# stm32f103.net
KiCad netlist of a schematic drawn in Altium Designer
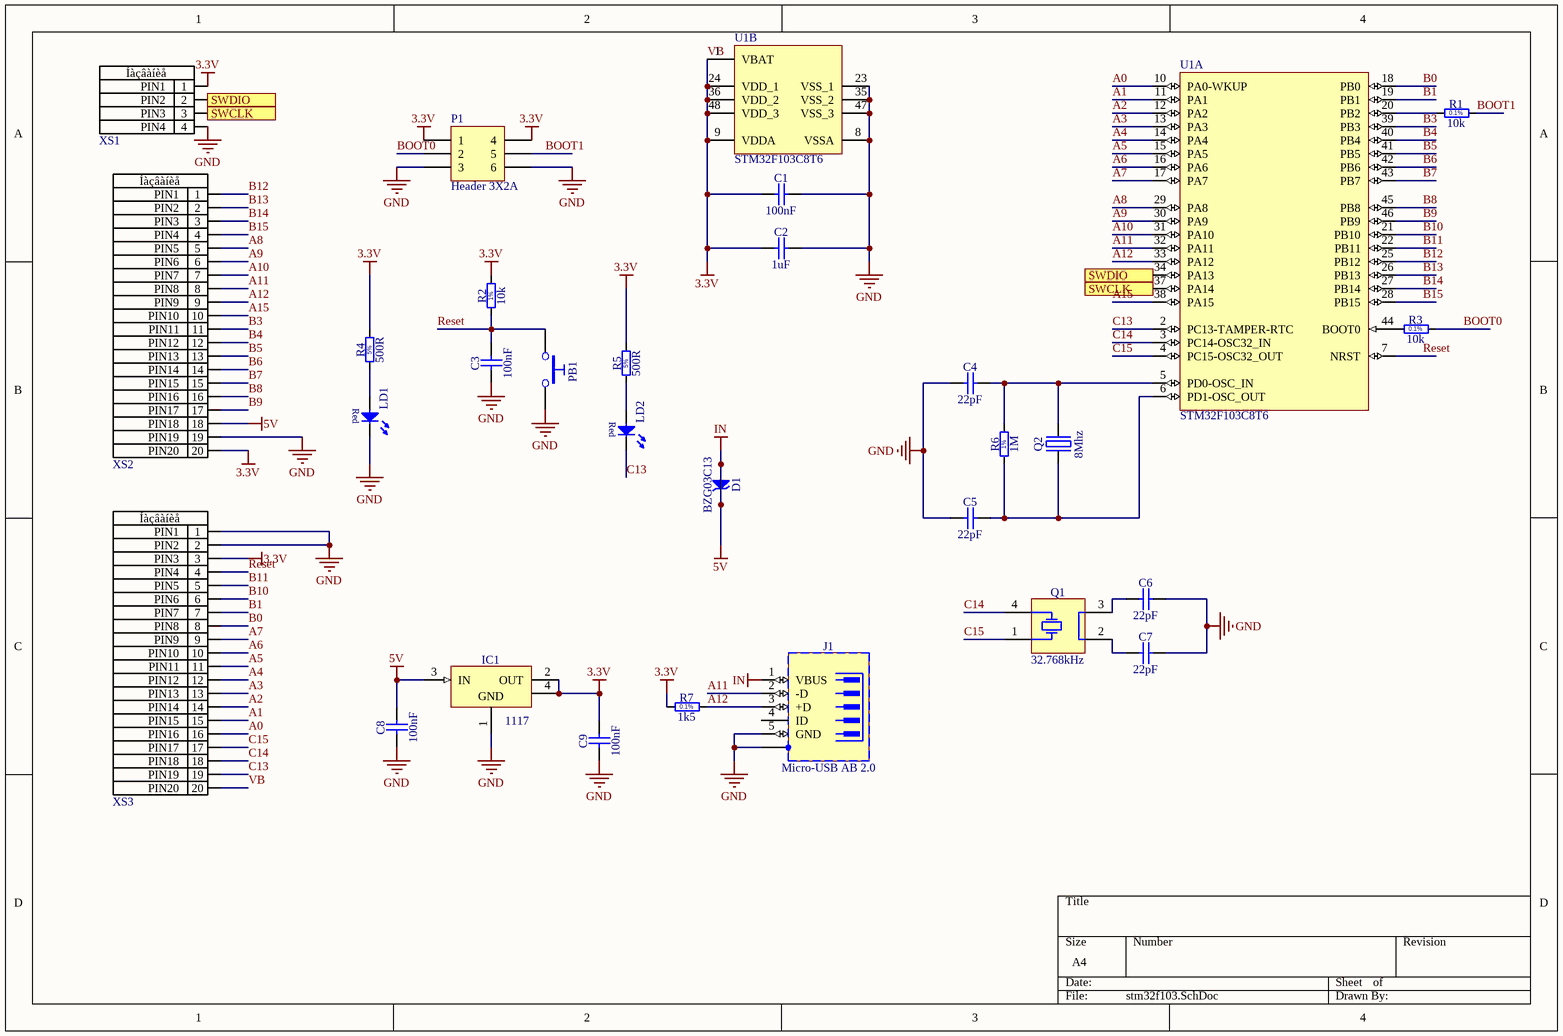
[diagram p0: stm32f103.SchDoc]

(export (version "E")
  (design (tool "Eeschema 10.0.6"))
  (components
    (comp (ref "C1")
      (value "100nF")
      (footprint "CAPC3216X140N")
      (description "Non-polarised capacitor")
      (fields
        (field (name "PART NUMBER") "CC1206_100NF_50V_10%_X7R")
        (field (name "VOLTAGE") "50V")
        (field (name "AUTHOR") "CERN DEM JLC")
      )
      (libsource (lib "Capacitors") (part "Capacitor - non polarized"))
    )
    (comp (ref "C2")
      (value "1uF")
      (footprint "CAPC3216X140N")
      (description "Non-polarised capacitor")
      (fields
        (field (name "PART NUMBER") "CC1206_1UF_50V_10%_X7R")
        (field (name "VOLTAGE") "50V")
        (field (name "AUTHOR") "CERN DEM JLC")
      )
      (libsource (lib "Capacitors") (part "Capacitor - non polarized"))
    )
    (comp (ref "C3")
      (value "100nF")
      (footprint "CAPC3216X140N")
      (description "Non-polarised capacitor")
      (fields
        (field (name "PART NUMBER") "CC1206_100NF_50V_10%_X7R")
        (field (name "VOLTAGE") "50V")
        (field (name "AUTHOR") "CERN DEM JLC")
      )
      (libsource (lib "Capacitors") (part "Capacitor - non polarized"))
    )
    (comp (ref "C4")
      (value "22pF")
      (footprint "CAPC3216X140N")
      (description "Non-polarised capacitor")
      (fields
        (field (name "PART NUMBER") "CC1206_12PF_50V_5%_NP0")
        (field (name "VOLTAGE") "50V")
        (field (name "AUTHOR") "CERN DEM JLC")
      )
      (libsource (lib "Capacitors") (part "Capacitor - non polarized"))
    )
    (comp (ref "C5")
      (value "22pF")
      (footprint "CAPC3216X140N")
      (description "Non-polarised capacitor")
      (fields
        (field (name "PART NUMBER") "CC1206_12PF_50V_5%_NP0")
        (field (name "VOLTAGE") "50V")
        (field (name "AUTHOR") "CERN DEM JLC")
      )
      (libsource (lib "Capacitors") (part "Capacitor - non polarized"))
    )
    (comp (ref "C6")
      (value "22pF")
      (footprint "CAPC3216X140N")
      (description "Non-polarised capacitor")
      (fields
        (field (name "PART NUMBER") "CC1206_100PF_50V_5%_NP0")
        (field (name "VOLTAGE") "50V")
        (field (name "AUTHOR") "CERN DEM JLC")
      )
      (libsource (lib "Capacitors") (part "Capacitor - non polarized"))
    )
    (comp (ref "C7")
      (value "22pF")
      (footprint "CAPC3216X140N")
      (description "Non-polarised capacitor")
      (fields
        (field (name "PART NUMBER") "CC1206_100PF_50V_5%_NP0")
        (field (name "VOLTAGE") "50V")
        (field (name "AUTHOR") "CERN DEM JLC")
      )
      (libsource (lib "Capacitors") (part "Capacitor - non polarized"))
    )
    (comp (ref "C8")
      (value "100nF")
      (footprint "CAPC3216X140N")
      (description "Non-polarised capacitor")
      (fields
        (field (name "PART NUMBER") "CC1206_100NF_50V_10%_X7R")
        (field (name "VOLTAGE") "50V")
        (field (name "AUTHOR") "CERN DEM JLC")
      )
      (libsource (lib "Capacitors") (part "Capacitor - non polarized"))
    )
    (comp (ref "C9")
      (value "100nF")
      (footprint "CAPC3216X140N")
      (description "Non-polarised capacitor")
      (fields
        (field (name "PART NUMBER") "CC1206_100NF_50V_10%_X7R")
        (field (name "VOLTAGE") "50V")
        (field (name "AUTHOR") "CERN DEM JLC")
      )
      (libsource (lib "Capacitors") (part "Capacitor - non polarized"))
    )
    (comp (ref "D1")
      (value "BZG03C13")
      (footprint "DIOM5326X230N")
      (description "Zener Diode")
      (fields
        (field (name "VOLTAGE") "13V")
        (field (name "POWER") "1.25W")
        (field (name "AUTHOR") "CERN DEM JLC")
      )
      (libsource (lib "ICs And Semiconductors") (part "Diode Zener"))
    )
    (comp (ref "IC1")
      (value "1117")
      (footprint "SOT230P700X180-4N")
      (description "3-Terminal Regulator 1=GND 2=OUT 3=IN 4=OUT")
      (fields
        (field (name "PART NUMBER") "ADP3339AKCZ-1.8")
        (field (name "MANUFACTURER") "ANALOG DEVICES")
        (field (name "AUTHOR") "CERN DEM BC")
      )
      (libsource (lib "ICs And Semiconductors") (part "REG3+1 1GND-2OUT-3IN+4OUT"))
    )
    (comp (ref "J1")
      (value "Micro-USB AB 2.0")
      (footprint "HIROSE_ZX62RD-AB-5P8(30)")
      (description "5 Pin + 1 Shield USB Receptacle")
      (fields
        (field (name "PART NUMBER") "HIROSE_ZX62RD-AB-5P8(30)")
        (field (name "MANUFACTURER") "HIROSE (HRS)")
        (field (name "AUTHOR") "CERN DEM JMW")
      )
      (libsource (lib "Connectors") (part "Connector USB 5 Pin + 1Shield"))
    )
    (comp (ref "LD1")
      (value "Red")
      (footprint "LED_DIALIGHT_597-3111-507F")
      (description "LED Red 1C 2A")
      (fields
        (field (name "PART NUMBER") "LED_DIALIGHT_597-3111-507F")
        (field (name "MANUFACTURER") "DIALIGHT")
        (field (name "AUTHOR") "CERN DEM JLC")
      )
      (libsource (lib "ICs And Semiconductors") (part "LED Red 1C 2A"))
    )
    (comp (ref "LD2")
      (value "Red")
      (footprint "LED_DIALIGHT_597-3111-507F")
      (description "LED Red 1C 2A")
      (fields
        (field (name "PART NUMBER") "LED_DIALIGHT_597-3111-507F")
        (field (name "MANUFACTURER") "DIALIGHT")
        (field (name "AUTHOR") "CERN DEM JLC")
      )
      (libsource (lib "ICs And Semiconductors") (part "LED Red 1C 2A"))
    )
    (comp (ref "P1")
      (value "Header 3X2A")
      (footprint "HDR2X3_CEN")
      (description "Header, 3-Pin, Dual row")
      (fields (field (name "PUBLISHER") "Altium Limited"))
      (libsource (lib "Miscellaneous Connectors") (part "Header 3X2A"))
    )
    (comp (ref "PB1")
      (value "Push Button")
      (footprint "PB_TYCO_FSMSM")
      (description "Push-Button Switch SPDT")
      (fields
        (field (name "PART NUMBER") "PB_TYCO_FSMSM")
        (field (name "MANUFACTURER") "TYCO ELECTRONICS")
        (field (name "AUTHOR") "CERN DEM JLC")
      )
      (libsource (lib "Eletro-mechanical") (part "PB SPST 1NO-2NO"))
    )
    (comp (ref "Q1")
      (value "32.768kHz")
      (footprint "XTAL_ABRACON_ABS25")
      (description "Crystal 4 pins 1=XTAL Control 2 And 3=NC 4=XTAL")
      (fields
        (field (name "PART NUMBER") "XTAL_32.768KHZ_ABRACON_ABS25-32.768KHZ-T")
        (field (name "MANUFACTURER") "ABRACON")
        (field (name "AUTHOR") "CERN DEM JMW")
      )
      (libsource (lib "ICs And Semiconductors") (part "Quartz Crystal 1X 2-3NC 4X"))
    )
    (comp (ref "Q2")
      (value "8Mhz")
      (footprint "XTAL1160X490X430")
      (description "Quartz Crystal")
      (fields
        (field (name "PART NUMBER") "XTAL_10MHZ_IQD_LFXTAL003166")
        (field (name "MANUFACTURER") "IQD FREQUENCY PRODUCTS")
        (field (name "AUTHOR") "CERN DEM JLC")
      )
      (libsource (lib "ICs And Semiconductors") (part "Quartz Crystal"))
    )
    (comp (ref "R1")
      (value "10k")
      (footprint "RESC1608X55N")
      (description "Resistor - 0.1%")
      (fields
        (field (name "PART NUMBER") "R0603_10K_0.1%_0.063W_10PPM")
        (field (name "POWER") "0.063W")
        (field (name "AUTHOR") "CERN DEM JLC")
      )
      (libsource (lib "Resistors") (part "Resistor - 0.1%"))
    )
    (comp (ref "R2")
      (value "10k")
      (footprint "RESC1608X55N")
      (description "Resistor - 1%")
      (fields
        (field (name "PART NUMBER") "R0603_10K_1%_0.1W_100PPM")
        (field (name "POWER") "0.1W")
        (field (name "AUTHOR") "CERN DEM JLC")
      )
      (libsource (lib "Resistors") (part "Resistor - 1%"))
    )
    (comp (ref "R3")
      (value "10k")
      (footprint "RESC1608X55N")
      (description "Resistor - 0.1%")
      (fields
        (field (name "PART NUMBER") "R0603_10K_0.1%_0.063W_10PPM")
        (field (name "POWER") "0.063W")
        (field (name "AUTHOR") "CERN DEM JLC")
      )
      (libsource (lib "Resistors") (part "Resistor - 0.1%"))
    )
    (comp (ref "R4")
      (value "500R")
      (footprint "RESC1509X55N")
      (description "Resistor - 5%")
      (fields
        (field (name "PART NUMBER") "R0603_500M_5%_0.1W_250PPM_OHMITE_HVC")
        (field (name "POWER") "0.1W")
        (field (name "AUTHOR") "CERN DEM JLC")
      )
      (libsource (lib "Resistors") (part "Resistor - 5%"))
    )
    (comp (ref "R5")
      (value "500R")
      (footprint "RESC1509X55N")
      (description "Resistor - 5%")
      (fields
        (field (name "PART NUMBER") "R0603_500M_5%_0.1W_250PPM_OHMITE_HVC")
        (field (name "POWER") "0.1W")
        (field (name "AUTHOR") "CERN DEM JLC")
      )
      (libsource (lib "Resistors") (part "Resistor - 5%"))
    )
    (comp (ref "R6")
      (value "1M")
      (footprint "RESC1608X55N")
      (description "Resistor - 1%")
      (fields
        (field (name "PART NUMBER") "R0603_1M_1%_0.1W_100PPM")
        (field (name "POWER") "0.1W")
        (field (name "AUTHOR") "CERN DEM JLC")
      )
      (libsource (lib "Resistors") (part "Resistor - 1%"))
    )
    (comp (ref "R7")
      (value "1k5")
      (footprint "RESC1608X55N")
      (description "Resistor - 0.1%")
      (fields
        (field (name "PART NUMBER") "R0603_1K5_0.1%_0.063W_10PPM")
        (field (name "POWER") "0.063W")
        (field (name "AUTHOR") "CERN DEM JLC")
      )
      (libsource (lib "Resistors") (part "Resistor - 0.1%"))
    )
    (comp (ref "U1")
      (value "STM32F103C8T6")
      (footprint "STM-LQFP48_N")
      (libsource (lib "STMicroelectronics STM32 F1") (part "STM32F103C8T6"))
    )
    (comp (ref "XS1")
      (value "Ğàçú¸ì PLS-4")
      (footprint "CeleronLib_Connect:HDR1X4 - WA")
      (description "Male, 4 pin single in line, 2.54")
      (fields (field (name "NAME") "Название"))
      (libsource (lib "CeleronLib_Connect") (part "HDR 1x4"))
    )
    (comp (ref "XS2")
      (value "Ğàçú¸ì PLS-20")
      (footprint "20SIN")
      (description "Male, 20 pin single in line, 2.54")
      (fields (field (name "NAME") "Название"))
      (libsource (lib "CeleronLib_Connect") (part "HDR 1x20"))
    )
    (comp (ref "XS3")
      (value "Ğàçú¸ì PLS-20")
      (footprint "20SIN")
      (description "Male, 20 pin single in line, 2.54")
      (fields (field (name "NAME") "Название"))
      (libsource (lib "CeleronLib_Connect") (part "HDR 1x20"))
    )
  )
  (nets
    (net (code "1") (name "/A0") (class "Default")
      (node (ref "U1") (pin "10") (pinfunction "PA0-WKUP_10") (pintype "bidirectional"))
      (node (ref "XS3") (pin "16") (pinfunction "PIN16_16") (pintype "passive"))
    )
    (net (code "2") (name "/A1") (class "Default")
      (node (ref "U1") (pin "11") (pinfunction "PA1_11") (pintype "bidirectional"))
      (node (ref "XS3") (pin "15") (pinfunction "PIN15_15") (pintype "passive"))
    )
    (net (code "3") (name "/A2") (class "Default")
      (node (ref "U1") (pin "12") (pinfunction "PA2_12") (pintype "bidirectional"))
      (node (ref "XS3") (pin "14") (pinfunction "PIN14_14") (pintype "passive"))
    )
    (net (code "4") (name "/A3") (class "Default")
      (node (ref "U1") (pin "13") (pinfunction "PA3_13") (pintype "bidirectional"))
      (node (ref "XS3") (pin "13") (pinfunction "PIN13_13") (pintype "passive"))
    )
    (net (code "5") (name "/A4") (class "Default")
      (node (ref "U1") (pin "14") (pinfunction "PA4_14") (pintype "bidirectional"))
      (node (ref "XS3") (pin "12") (pinfunction "PIN12_12") (pintype "passive"))
    )
    (net (code "6") (name "/A5") (class "Default")
      (node (ref "U1") (pin "15") (pinfunction "PA5_15") (pintype "bidirectional"))
      (node (ref "XS3") (pin "11") (pinfunction "PIN11_11") (pintype "passive"))
    )
    (net (code "7") (name "/A6") (class "Default")
      (node (ref "U1") (pin "16") (pinfunction "PA6_16") (pintype "bidirectional"))
      (node (ref "XS3") (pin "10") (pinfunction "PIN10_10") (pintype "passive"))
    )
    (net (code "8") (name "/A7") (class "Default")
      (node (ref "U1") (pin "17") (pinfunction "PA7_17") (pintype "bidirectional"))
      (node (ref "XS3") (pin "9") (pinfunction "PIN9_9") (pintype "passive"))
    )
    (net (code "9") (name "/A8") (class "Default")
      (node (ref "U1") (pin "29") (pinfunction "PA8_29") (pintype "bidirectional"))
      (node (ref "XS2") (pin "5") (pinfunction "PIN5_5") (pintype "passive"))
    )
    (net (code "10") (name "/A9") (class "Default")
      (node (ref "U1") (pin "30") (pinfunction "PA9_30") (pintype "bidirectional"))
      (node (ref "XS2") (pin "6") (pinfunction "PIN6_6") (pintype "passive"))
    )
    (net (code "11") (name "/A10") (class "Default")
      (node (ref "U1") (pin "31") (pinfunction "PA10_31") (pintype "bidirectional"))
      (node (ref "XS2") (pin "7") (pinfunction "PIN7_7") (pintype "passive"))
    )
    (net (code "12") (name "/A11") (class "Default")
      (node (ref "J1") (pin "2") (pinfunction "-D_2") (pintype "bidirectional"))
      (node (ref "U1") (pin "32") (pinfunction "PA11_32") (pintype "bidirectional"))
      (node (ref "XS2") (pin "8") (pinfunction "PIN8_8") (pintype "passive"))
    )
    (net (code "13") (name "/A12") (class "Default")
      (node (ref "J1") (pin "3") (pinfunction "+D_3") (pintype "bidirectional"))
      (node (ref "R7") (pin "2") (pinfunction "2_2") (pintype "passive"))
      (node (ref "U1") (pin "33") (pinfunction "PA12_33") (pintype "bidirectional"))
      (node (ref "XS2") (pin "9") (pinfunction "PIN9_9") (pintype "passive"))
    )
    (net (code "14") (name "/A15") (class "Default")
      (node (ref "U1") (pin "38") (pinfunction "PA15_38") (pintype "bidirectional"))
      (node (ref "XS2") (pin "10") (pinfunction "PIN10_10") (pintype "passive"))
    )
    (net (code "15") (name "/B0") (class "Default")
      (node (ref "U1") (pin "18") (pinfunction "PB0_18") (pintype "bidirectional"))
      (node (ref "XS3") (pin "8") (pinfunction "PIN8_8") (pintype "passive"))
    )
    (net (code "16") (name "/B1") (class "Default")
      (node (ref "U1") (pin "19") (pinfunction "PB1_19") (pintype "bidirectional"))
      (node (ref "XS3") (pin "7") (pinfunction "PIN7_7") (pintype "passive"))
    )
    (net (code "17") (name "/B3") (class "Default")
      (node (ref "U1") (pin "39") (pinfunction "PB3_39") (pintype "bidirectional"))
      (node (ref "XS2") (pin "11") (pinfunction "PIN11_11") (pintype "passive"))
    )
    (net (code "18") (name "/B4") (class "Default")
      (node (ref "U1") (pin "40") (pinfunction "PB4_40") (pintype "bidirectional"))
      (node (ref "XS2") (pin "12") (pinfunction "PIN12_12") (pintype "passive"))
    )
    (net (code "19") (name "/B5") (class "Default")
      (node (ref "U1") (pin "41") (pinfunction "PB5_41") (pintype "bidirectional"))
      (node (ref "XS2") (pin "13") (pinfunction "PIN13_13") (pintype "passive"))
    )
    (net (code "20") (name "/B6") (class "Default")
      (node (ref "U1") (pin "42") (pinfunction "PB6_42") (pintype "bidirectional"))
      (node (ref "XS2") (pin "14") (pinfunction "PIN14_14") (pintype "passive"))
    )
    (net (code "21") (name "/B7") (class "Default")
      (node (ref "U1") (pin "43") (pinfunction "PB7_43") (pintype "bidirectional"))
      (node (ref "XS2") (pin "15") (pinfunction "PIN15_15") (pintype "passive"))
    )
    (net (code "22") (name "/B8") (class "Default")
      (node (ref "U1") (pin "45") (pinfunction "PB8_45") (pintype "bidirectional"))
      (node (ref "XS2") (pin "16") (pinfunction "PIN16_16") (pintype "passive"))
    )
    (net (code "23") (name "/B9") (class "Default")
      (node (ref "U1") (pin "46") (pinfunction "PB9_46") (pintype "bidirectional"))
      (node (ref "XS2") (pin "17") (pinfunction "PIN17_17") (pintype "passive"))
    )
    (net (code "24") (name "/B10") (class "Default")
      (node (ref "U1") (pin "21") (pinfunction "PB10_21") (pintype "bidirectional"))
      (node (ref "XS3") (pin "6") (pinfunction "PIN6_6") (pintype "passive"))
    )
    (net (code "25") (name "/B11") (class "Default")
      (node (ref "U1") (pin "22") (pinfunction "PB11_22") (pintype "bidirectional"))
      (node (ref "XS3") (pin "5") (pinfunction "PIN5_5") (pintype "passive"))
    )
    (net (code "26") (name "/B12") (class "Default")
      (node (ref "U1") (pin "25") (pinfunction "PB12_25") (pintype "bidirectional"))
      (node (ref "XS2") (pin "1") (pinfunction "PIN1_1") (pintype "passive"))
    )
    (net (code "27") (name "/B13") (class "Default")
      (node (ref "U1") (pin "26") (pinfunction "PB13_26") (pintype "bidirectional"))
      (node (ref "XS2") (pin "2") (pinfunction "PIN2_2") (pintype "passive"))
    )
    (net (code "28") (name "/B14") (class "Default")
      (node (ref "U1") (pin "27") (pinfunction "PB14_27") (pintype "bidirectional"))
      (node (ref "XS2") (pin "3") (pinfunction "PIN3_3") (pintype "passive"))
    )
    (net (code "29") (name "/B15") (class "Default")
      (node (ref "U1") (pin "28") (pinfunction "PB15_28") (pintype "bidirectional"))
      (node (ref "XS2") (pin "4") (pinfunction "PIN4_4") (pintype "passive"))
    )
    (net (code "30") (name "/BOOT0") (class "Default")
      (node (ref "P1") (pin "2") (pinfunction "2_2") (pintype "passive"))
      (node (ref "R3") (pin "2") (pinfunction "2_2") (pintype "passive"))
    )
    (net (code "31") (name "/BOOT1") (class "Default")
      (node (ref "P1") (pin "5") (pinfunction "5_5") (pintype "passive"))
      (node (ref "R1") (pin "2") (pinfunction "2_2") (pintype "passive"))
    )
    (net (code "32") (name "/C13") (class "Default")
      (node (ref "LD2") (pin "1") (pinfunction "C_1") (pintype "passive"))
      (node (ref "U1") (pin "2") (pinfunction "PC13-TAMPER-RTC_2") (pintype "bidirectional"))
      (node (ref "XS3") (pin "19") (pinfunction "PIN19_19") (pintype "passive"))
    )
    (net (code "33") (name "/C14") (class "Default")
      (node (ref "Q1") (pin "4") (pinfunction "X_4") (pintype "passive"))
      (node (ref "U1") (pin "3") (pinfunction "PC14-OSC32_IN_3") (pintype "bidirectional"))
      (node (ref "XS3") (pin "18") (pinfunction "PIN18_18") (pintype "passive"))
    )
    (net (code "34") (name "/C15") (class "Default")
      (node (ref "Q1") (pin "1") (pinfunction "X_1") (pintype "passive"))
      (node (ref "U1") (pin "4") (pinfunction "PC15-OSC32_OUT_4") (pintype "bidirectional"))
      (node (ref "XS3") (pin "17") (pinfunction "PIN17_17") (pintype "passive"))
    )
    (net (code "35") (name "/Reset") (class "Default")
      (node (ref "C3") (pin "2") (pinfunction "2_2") (pintype "passive"))
      (node (ref "PB1") (pin "1") (pinfunction "1_1") (pintype "passive"))
      (node (ref "R2") (pin "1") (pinfunction "1_1") (pintype "passive"))
      (node (ref "U1") (pin "7") (pinfunction "NRST_7") (pintype "bidirectional"))
      (node (ref "XS3") (pin "4") (pinfunction "PIN4_4") (pintype "passive"))
    )
    (net (code "36") (name "/SWCLK") (class "Default")
      (node (ref "U1") (pin "37") (pinfunction "PA14_37") (pintype "bidirectional"))
      (node (ref "XS1") (pin "3") (pinfunction "PIN3_3") (pintype "passive"))
    )
    (net (code "37") (name "/SWDIO") (class "Default")
      (node (ref "U1") (pin "34") (pinfunction "PA13_34") (pintype "bidirectional"))
      (node (ref "XS1") (pin "2") (pinfunction "PIN2_2") (pintype "passive"))
    )
    (net (code "38") (name "3.3V") (class "Default")
      (node (ref "C1") (pin "1") (pinfunction "1_1") (pintype "passive"))
      (node (ref "C2") (pin "1") (pinfunction "1_1") (pintype "passive"))
      (node (ref "C9") (pin "2") (pinfunction "2_2") (pintype "passive"))
      (node (ref "IC1") (pin "2") (pinfunction "OUT_2") (pintype "power_in"))
      (node (ref "IC1") (pin "4") (pinfunction "OUT_4") (pintype "power_in"))
      (node (ref "P1") (pin "1") (pinfunction "1_1") (pintype "passive"))
      (node (ref "P1") (pin "4") (pinfunction "4_4") (pintype "passive"))
      (node (ref "R2") (pin "2") (pinfunction "2_2") (pintype "passive"))
      (node (ref "R4") (pin "2") (pinfunction "2_2") (pintype "passive"))
      (node (ref "R5") (pin "2") (pinfunction "2_2") (pintype "passive"))
      (node (ref "R7") (pin "1") (pinfunction "1_1") (pintype "passive"))
      (node (ref "U1") (pin "1") (pinfunction "VBAT_1") (pintype "power_in"))
      (node (ref "U1") (pin "24") (pinfunction "VDD_1_24") (pintype "power_in"))
      (node (ref "U1") (pin "36") (pinfunction "VDD_2_36") (pintype "power_in"))
      (node (ref "U1") (pin "48") (pinfunction "VDD_3_48") (pintype "power_in"))
      (node (ref "U1") (pin "9") (pinfunction "VDDA_9") (pintype "power_in"))
      (node (ref "XS1") (pin "1") (pinfunction "PIN1_1") (pintype "passive"))
      (node (ref "XS2") (pin "20") (pinfunction "PIN20_20") (pintype "passive"))
      (node (ref "XS3") (pin "20") (pinfunction "PIN20_20") (pintype "passive"))
      (node (ref "XS3") (pin "3") (pinfunction "PIN3_3") (pintype "passive"))
    )
    (net (code "39") (name "5V") (class "Default")
      (node (ref "C8") (pin "2") (pinfunction "2_2") (pintype "passive"))
      (node (ref "D1") (pin "1") (pinfunction "C_1") (pintype "passive"))
      (node (ref "D1") (pin "2") (pinfunction "A_2") (pintype "passive"))
      (node (ref "IC1") (pin "3") (pinfunction "IN_3") (pintype "input"))
      (node (ref "J1") (pin "1") (pinfunction "VBUS_1") (pintype "bidirectional"))
      (node (ref "XS2") (pin "18") (pinfunction "PIN18_18") (pintype "passive"))
    )
    (net (code "40") (name "GND") (class "Default")
      (node (ref "C1") (pin "2") (pinfunction "2_2") (pintype "passive"))
      (node (ref "C2") (pin "2") (pinfunction "2_2") (pintype "passive"))
      (node (ref "C3") (pin "1") (pinfunction "1_1") (pintype "passive"))
      (node (ref "C4") (pin "1") (pinfunction "1_1") (pintype "passive"))
      (node (ref "C5") (pin "1") (pinfunction "1_1") (pintype "passive"))
      (node (ref "C6") (pin "2") (pinfunction "2_2") (pintype "passive"))
      (node (ref "C7") (pin "2") (pinfunction "2_2") (pintype "passive"))
      (node (ref "C8") (pin "1") (pinfunction "1_1") (pintype "passive"))
      (node (ref "C9") (pin "1") (pinfunction "1_1") (pintype "passive"))
      (node (ref "IC1") (pin "1") (pinfunction "GND_1") (pintype "power_in"))
      (node (ref "J1") (pin "5") (pinfunction "GND_5") (pintype "bidirectional"))
      (node (ref "J1") (pin "6") (pinfunction "SH_6") (pintype "power_in"))
      (node (ref "LD1") (pin "1") (pinfunction "C_1") (pintype "passive"))
      (node (ref "P1") (pin "3") (pinfunction "3_3") (pintype "passive"))
      (node (ref "P1") (pin "6") (pinfunction "6_6") (pintype "passive"))
      (node (ref "PB1") (pin "2") (pinfunction "2_2") (pintype "passive"))
      (node (ref "U1") (pin "23") (pinfunction "VSS_1_23") (pintype "power_in"))
      (node (ref "U1") (pin "35") (pinfunction "VSS_2_35") (pintype "power_in"))
      (node (ref "U1") (pin "47") (pinfunction "VSS_3_47") (pintype "power_in"))
      (node (ref "U1") (pin "8") (pinfunction "VSSA_8") (pintype "power_in"))
      (node (ref "XS1") (pin "4") (pinfunction "PIN4_4") (pintype "passive"))
      (node (ref "XS2") (pin "19") (pinfunction "PIN19_19") (pintype "passive"))
      (node (ref "XS3") (pin "1") (pinfunction "PIN1_1") (pintype "passive"))
      (node (ref "XS3") (pin "2") (pinfunction "PIN2_2") (pintype "passive"))
    )
    (net (code "41") (name "Net-(C6-Pad1)") (class "Default")
      (node (ref "C6") (pin "1") (pinfunction "1_1") (pintype "passive"))
      (node (ref "Q1") (pin "3") (pinfunction "GND_3") (pintype "power_in"))
    )
    (net (code "42") (name "Net-(C7-Pad1)") (class "Default")
      (node (ref "C7") (pin "1") (pinfunction "1_1") (pintype "passive"))
      (node (ref "Q1") (pin "2") (pinfunction "GND_2") (pintype "power_in"))
    )
    (net (code "43") (name "Net-(LD1-A)") (class "Default")
      (node (ref "LD1") (pin "2") (pinfunction "A_2") (pintype "passive"))
      (node (ref "R4") (pin "1") (pinfunction "1_1") (pintype "passive"))
    )
    (net (code "44") (name "Net-(LD2-A)") (class "Default")
      (node (ref "LD2") (pin "2") (pinfunction "A_2") (pintype "passive"))
      (node (ref "R5") (pin "1") (pinfunction "1_1") (pintype "passive"))
    )
    (net (code "45") (name "Net-(Q2-OSC1)") (class "Default")
      (node (ref "C5") (pin "2") (pinfunction "2_2") (pintype "passive"))
      (node (ref "Q2") (pin "1") (pinfunction "OSC1_1") (pintype "passive"))
      (node (ref "R6") (pin "1") (pinfunction "1_1") (pintype "passive"))
      (node (ref "U1") (pin "6") (pinfunction "PD1-OSC_OUT_6") (pintype "bidirectional"))
    )
    (net (code "46") (name "Net-(Q2-OSC2)") (class "Default")
      (node (ref "C4") (pin "2") (pinfunction "2_2") (pintype "passive"))
      (node (ref "Q2") (pin "2") (pinfunction "OSC2_2") (pintype "passive"))
      (node (ref "R6") (pin "2") (pinfunction "2_2") (pintype "passive"))
      (node (ref "U1") (pin "5") (pinfunction "PD0-OSC_IN_5") (pintype "bidirectional"))
    )
    (net (code "47") (name "Net-(U1A-BOOT0)") (class "Default")
      (node (ref "R3") (pin "1") (pinfunction "1_1") (pintype "passive"))
      (node (ref "U1") (pin "44") (pinfunction "BOOT0_44") (pintype "input"))
    )
    (net (code "48") (name "Net-(U1A-PB2)") (class "Default")
      (node (ref "R1") (pin "1") (pinfunction "1_1") (pintype "passive"))
      (node (ref "U1") (pin "20") (pinfunction "PB2_20") (pintype "bidirectional"))
    )
    (net (code "49") (name "unconnected-(J1-ID-Pad4)") (class "Default")
      (node (ref "J1") (pin "4") (pinfunction "ID_4") (pintype "passive"))
    )
  )
)
